# solar-shield.net
KiCad netlist of a schematic drawn in EAGLE
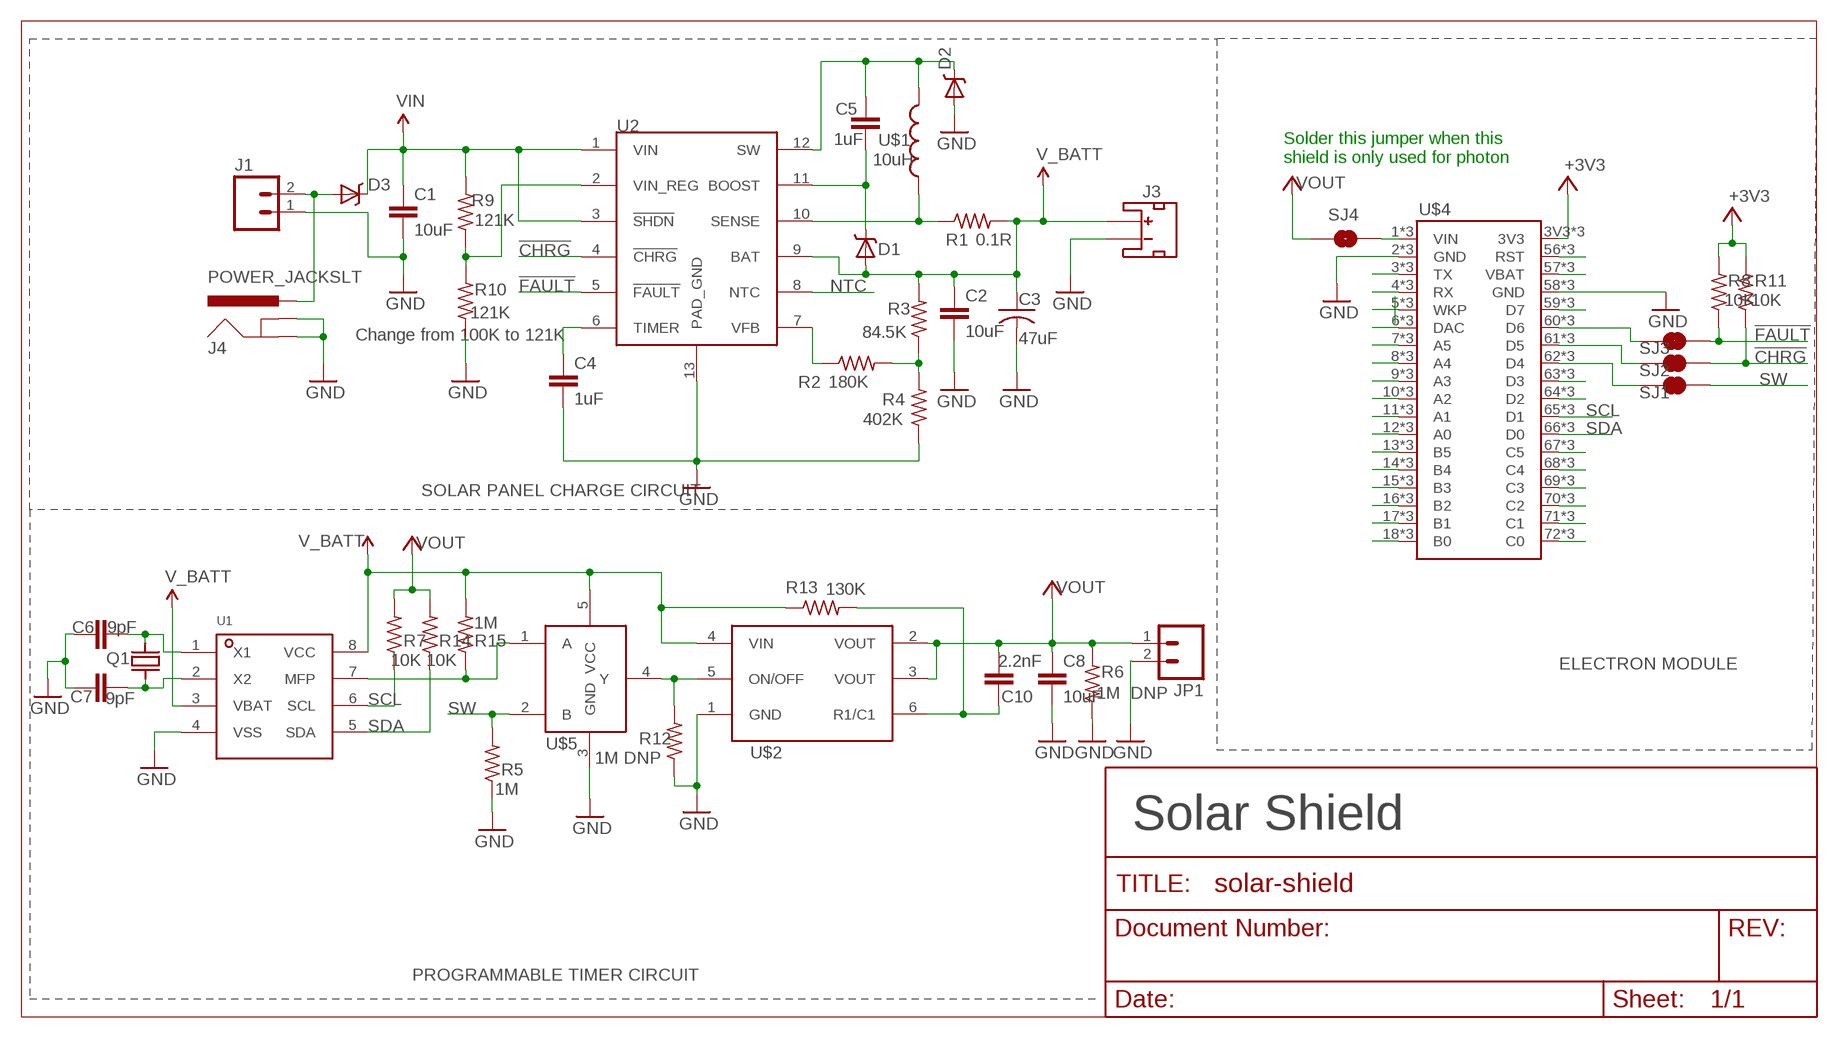
[diagram p0: schematic, sheet 1]

(export (version "E")
  (design (tool "Eeschema 10.0.6"))
  (components
    (comp (ref "C1")
      (value "10uF")
      (footprint "eagle-import:1206")
      (libsource (lib "eagle-import") (part "CAP_NONE_POLB"))
    )
    (comp (ref "C2")
      (value "10uF")
      (footprint "eagle-import:1206")
      (libsource (lib "eagle-import") (part "CAP_NONE_POLB"))
    )
    (comp (ref "C3")
      (value "47uF")
      (footprint "eagle-import:47U_TAN")
      (libsource (lib "eagle-import") (part "C-USB"))
    )
    (comp (ref "C4")
      (value "1uF")
      (footprint "eagle-import:0603")
      (libsource (lib "eagle-import") (part "CAP_NONE_POL"))
    )
    (comp (ref "C5")
      (value "1uF")
      (footprint "eagle-import:0603")
      (libsource (lib "eagle-import") (part "CAP_NONE_POL"))
    )
    (comp (ref "C6")
      (value "9pF")
      (footprint "eagle-import:0603")
      (libsource (lib "eagle-import") (part "CAP_NONE_POL"))
    )
    (comp (ref "C7")
      (value "9pF")
      (footprint "eagle-import:0603")
      (libsource (lib "eagle-import") (part "CAP_NONE_POL"))
    )
    (comp (ref "C8")
      (value "10uF")
      (footprint "eagle-import:0805")
      (libsource (lib "eagle-import") (part "CAP_NONE_POLA"))
    )
    (comp (ref "C10")
      (value "2.2nF")
      (footprint "eagle-import:0603")
      (libsource (lib "eagle-import") (part "CAP_NONE_POL"))
    )
    (comp (ref "D1")
      (value "DIODE_SCHOTTKYD")
      (footprint "eagle-import:DIODE_SOD323")
      (libsource (lib "eagle-import") (part "DIODE_SCHOTTKYD"))
    )
    (comp (ref "D2")
      (value "DIODE_SCHOTTKYA")
      (footprint "eagle-import:DIODE_SMA")
      (libsource (lib "eagle-import") (part "DIODE_SCHOTTKYA"))
    )
    (comp (ref "D3")
      (value "DIODE_SCHOTTKYA")
      (footprint "eagle-import:DIODE_SMA")
      (libsource (lib "eagle-import") (part "DIODE_SCHOTTKYA"))
    )
    (comp (ref "J1")
      (value "M025MM")
      (footprint "eagle-import:SCREWTERMINAL-5MM-2")
      (libsource (lib "eagle-import") (part "M025MM"))
    )
    (comp (ref "J3")
      (value "JST_2MM_MALEA")
      (footprint "eagle-import:JST_2_MSD_VERT")
      (libsource (lib "eagle-import") (part "JST_2MM_MALEA"))
    )
    (comp (ref "J4")
      (value "POWER_JACKSLT")
      (footprint "eagle-import:POWER_JACK_SLOT")
      (libsource (lib "eagle-import") (part "POWER_JACKSLT"))
    )
    (comp (ref "JP1")
      (value "M02PTH")
      (footprint "eagle-import:1X02")
      (libsource (lib "eagle-import") (part "M02PTH"))
    )
    (comp (ref "Q1")
      (value "Q_FC135")
      (footprint "eagle-import:FC135")
      (libsource (lib "eagle-import") (part "Q_FC135"))
    )
    (comp (ref "R1")
      (value "0.1R")
      (footprint "eagle-import:R0805")
      (libsource (lib "eagle-import") (part "R-US_B"))
    )
    (comp (ref "R2")
      (value "180K")
      (footprint "eagle-import:0603")
      (libsource (lib "eagle-import") (part "R_0603"))
    )
    (comp (ref "R3")
      (value "84.5K")
      (footprint "eagle-import:0603")
      (libsource (lib "eagle-import") (part "R_0603"))
    )
    (comp (ref "R4")
      (value "402K")
      (footprint "eagle-import:0603")
      (libsource (lib "eagle-import") (part "R_0603"))
    )
    (comp (ref "R5")
      (value "1M")
      (footprint "eagle-import:0603")
      (libsource (lib "eagle-import") (part "R_0603"))
    )
    (comp (ref "R6")
      (value "1M DNP")
      (footprint "eagle-import:0603")
      (libsource (lib "eagle-import") (part "R_0603"))
    )
    (comp (ref "R7")
      (value "10K")
      (footprint "eagle-import:0603")
      (libsource (lib "eagle-import") (part "R_0603"))
    )
    (comp (ref "R8")
      (value "10K")
      (footprint "eagle-import:0603")
      (libsource (lib "eagle-import") (part "R_0603"))
    )
    (comp (ref "R9")
      (value "121K")
      (footprint "eagle-import:0603")
      (libsource (lib "eagle-import") (part "R_0603"))
    )
    (comp (ref "R10")
      (value "121K")
      (footprint "eagle-import:0603")
      (libsource (lib "eagle-import") (part "R_0603"))
    )
    (comp (ref "R11")
      (value "10K")
      (footprint "eagle-import:0603")
      (libsource (lib "eagle-import") (part "R_0603"))
    )
    (comp (ref "R12")
      (value "1M DNP")
      (footprint "eagle-import:0603")
      (libsource (lib "eagle-import") (part "R_0603"))
    )
    (comp (ref "R13")
      (value "130K")
      (footprint "eagle-import:0603")
      (libsource (lib "eagle-import") (part "R_0603"))
    )
    (comp (ref "R14")
      (value "10K")
      (footprint "eagle-import:0603")
      (libsource (lib "eagle-import") (part "R_0603"))
    )
    (comp (ref "R15")
      (value "1M")
      (footprint "eagle-import:0603")
      (libsource (lib "eagle-import") (part "R_0603"))
    )
    (comp (ref "SJ1")
      (value "JUMPER-PAD-2-NC_BY_TRACE")
      (footprint "eagle-import:PAD-JUMPER-2-NC_BY_TRACE_YES_SILK")
      (libsource (lib "eagle-import") (part "JUMPER-PAD-2-NC_BY_TRACE"))
    )
    (comp (ref "SJ2")
      (value "JUMPER-PAD-2-NC_BY_TRACE")
      (footprint "eagle-import:PAD-JUMPER-2-NC_BY_TRACE_YES_SILK")
      (libsource (lib "eagle-import") (part "JUMPER-PAD-2-NC_BY_TRACE"))
    )
    (comp (ref "SJ3")
      (value "JUMPER-PAD-2-NC_BY_TRACE")
      (footprint "eagle-import:PAD-JUMPER-2-NC_BY_TRACE_YES_SILK")
      (libsource (lib "eagle-import") (part "JUMPER-PAD-2-NC_BY_TRACE"))
    )
    (comp (ref "SJ4")
      (value "JUMPER-PAD-2-NO")
      (footprint "eagle-import:PAD-JUMPER-2-NO_NO_SILK")
      (libsource (lib "eagle-import") (part "JUMPER-PAD-2-NO"))
    )
    (comp (ref "U$1")
      (value "10uH")
      (footprint "eagle-import:INDUCTOR_NR6045T100M")
      (libsource (lib "eagle-import") (part "INDUCTORR"))
    )
    (comp (ref "U$2")
      (value "TPS27082L")
      (footprint "eagle-import:TPS27082L")
      (libsource (lib "eagle-import") (part "TPS27082L"))
    )
    (comp (ref "U$4")
      (value "ELECTRONDUALROW")
      (footprint "eagle-import:ELECTRON_DUAL-ROW")
      (libsource (lib "eagle-import") (part "ELECTRONDUALROW"))
    )
    (comp (ref "U$5")
      (value "SN74UP1G32A")
      (footprint "eagle-import:SN74UP1G32_DBV")
      (libsource (lib "eagle-import") (part "SN74UP1G32A"))
    )
    (comp (ref "U1")
      (value "RTC_MCP7941X")
      (footprint "eagle-import:RTC_MCP7941X")
      (libsource (lib "eagle-import") (part "RTC_MCP7941X"))
    )
    (comp (ref "U2")
      (value "LT3652A")
      (footprint "eagle-import:DFN_3X3")
      (libsource (lib "eagle-import") (part "LT3652A"))
    )
  )
  (nets
    (net (code "1") (name "+3V3") (class "Default")
      (node (ref "R11") (pin "2") (pinfunction "2_2") (pintype "passive"))
      (node (ref "R8") (pin "2") (pinfunction "2_2") (pintype "passive"))
      (node (ref "U$4") (pin "3V3") (pinfunction "3V3_3V3") (pintype "power_in"))
      (node (ref "U$4") (pin "55") (pinfunction "3V3_55") (pintype "power_in"))
      (node (ref "U$4") (pin "91") (pinfunction "3V3_91") (pintype "power_in"))
    )
    (net (code "2") (name "/N$10") (class "Default")
      (node (ref "U$4") (pin "3") (pinfunction "TX_3") (pintype "bidirectional"))
      (node (ref "U$4") (pin "39") (pinfunction "TX_39") (pintype "bidirectional"))
      (node (ref "U$4") (pin "TX") (pinfunction "TX_TX") (pintype "bidirectional"))
    )
    (net (code "3") (name "/NTC") (class "Default")
      (node (ref "U2") (pin "8") (pinfunction "NTC_8") (pintype "bidirectional"))
    )
    (net (code "4") (name "/SCL") (class "Default")
      (node (ref "R7") (pin "1") (pinfunction "1_1") (pintype "passive"))
      (node (ref "U$4") (pin "101") (pinfunction "D1_101") (pintype "bidirectional"))
      (node (ref "U$4") (pin "65") (pinfunction "D1_65") (pintype "bidirectional"))
      (node (ref "U$4") (pin "D1") (pinfunction "D1_D1") (pintype "bidirectional"))
      (node (ref "U1") (pin "6") (pinfunction "SCL_6") (pintype "bidirectional"))
    )
    (net (code "5") (name "/SDA") (class "Default")
      (node (ref "R14") (pin "1") (pinfunction "1_1") (pintype "passive"))
      (node (ref "U$4") (pin "102") (pinfunction "D0_102") (pintype "bidirectional"))
      (node (ref "U$4") (pin "66") (pinfunction "D0_66") (pintype "bidirectional"))
      (node (ref "U$4") (pin "D0") (pinfunction "D0_D0") (pintype "bidirectional"))
      (node (ref "U1") (pin "5") (pinfunction "SDA_5") (pintype "bidirectional"))
    )
    (net (code "6") (name "/SW") (class "Default")
      (node (ref "R5") (pin "2") (pinfunction "2_2") (pintype "passive"))
      (node (ref "SJ1") (pin "2") (pinfunction "2_2") (pintype "passive"))
      (node (ref "U$5") (pin "2") (pinfunction "B_2") (pintype "bidirectional"))
    )
    (net (code "7") (name "/~{CHRG}") (class "Default")
      (node (ref "R11") (pin "1") (pinfunction "1_1") (pintype "passive"))
      (node (ref "SJ2") (pin "2") (pinfunction "2_2") (pintype "passive"))
      (node (ref "U2") (pin "4") (pinfunction "~{CHRG}_4") (pintype "bidirectional"))
    )
    (net (code "8") (name "/~{FAULT}") (class "Default")
      (node (ref "R8") (pin "1") (pinfunction "1_1") (pintype "passive"))
      (node (ref "SJ3") (pin "2") (pinfunction "2_2") (pintype "passive"))
      (node (ref "U2") (pin "5") (pinfunction "~{FAULT}_5") (pintype "bidirectional"))
    )
    (net (code "9") (name "GND") (class "Default")
      (node (ref "C1") (pin "2") (pinfunction "CATHODE_2") (pintype "passive"))
      (node (ref "C2") (pin "2") (pinfunction "CATHODE_2") (pintype "passive"))
      (node (ref "C3") (pin "C") (pinfunction "2_C") (pintype "passive"))
      (node (ref "C4") (pin "2") (pinfunction "CATHODE_2") (pintype "passive"))
      (node (ref "C6") (pin "1") (pinfunction "ANODE_1") (pintype "passive"))
      (node (ref "C7") (pin "1") (pinfunction "ANODE_1") (pintype "passive"))
      (node (ref "C8") (pin "2") (pinfunction "CATHODE_2") (pintype "passive"))
      (node (ref "D2") (pin "ANODE") (pinfunction "ANODE_ANODE") (pintype "passive"))
      (node (ref "J1") (pin "1") (pinfunction "1_1") (pintype "passive"))
      (node (ref "J3") (pin "GND") (pinfunction "-_GND") (pintype "bidirectional"))
      (node (ref "J4") (pin "GND@1") (pinfunction "GNDBREAK_GND@1") (pintype "bidirectional"))
      (node (ref "J4") (pin "GND@2") (pinfunction "GND_GND@2") (pintype "bidirectional"))
      (node (ref "JP1") (pin "2") (pinfunction "2_2") (pintype "passive"))
      (node (ref "R10") (pin "1") (pinfunction "1_1") (pintype "passive"))
      (node (ref "R12") (pin "1") (pinfunction "1_1") (pintype "passive"))
      (node (ref "R4") (pin "1") (pinfunction "1_1") (pintype "passive"))
      (node (ref "R5") (pin "1") (pinfunction "1_1") (pintype "passive"))
      (node (ref "R6") (pin "1") (pinfunction "1_1") (pintype "passive"))
      (node (ref "U$2") (pin "1") (pinfunction "GND_1") (pintype "bidirectional"))
      (node (ref "U$4") (pin "2") (pinfunction "GND_2") (pintype "power_in"))
      (node (ref "U$4") (pin "38") (pinfunction "GND_38") (pintype "power_in"))
      (node (ref "U$4") (pin "58") (pinfunction "GND_58") (pintype "power_in"))
      (node (ref "U$4") (pin "94") (pinfunction "GND_94") (pintype "power_in"))
      (node (ref "U$4") (pin "GND") (pinfunction "GND_GND") (pintype "power_in"))
      (node (ref "U$4") (pin "GND@2") (pinfunction "GND_GND@2") (pintype "power_in"))
      (node (ref "U$5") (pin "3") (pinfunction "GND_3") (pintype "bidirectional"))
      (node (ref "U1") (pin "4") (pinfunction "VSS_4") (pintype "bidirectional"))
      (node (ref "U2") (pin "13") (pinfunction "PAD_GND_13") (pintype "bidirectional"))
    )
    (net (code "10") (name "Net-(C4-ANODE)") (class "Default")
      (node (ref "C4") (pin "1") (pinfunction "ANODE_1") (pintype "passive"))
      (node (ref "U2") (pin "6") (pinfunction "TIMER_6") (pintype "bidirectional"))
    )
    (net (code "11") (name "Net-(C5-ANODE)") (class "Default")
      (node (ref "C5") (pin "1") (pinfunction "ANODE_1") (pintype "passive"))
      (node (ref "D2") (pin "CATHODE") (pinfunction "CATHODE_CATHODE") (pintype "passive"))
      (node (ref "U$1") (pin "P$2") (pinfunction "2_P$2") (pintype "passive"))
      (node (ref "U2") (pin "12") (pinfunction "SW_12") (pintype "bidirectional"))
    )
    (net (code "12") (name "Net-(C5-CATHODE)") (class "Default")
      (node (ref "C5") (pin "2") (pinfunction "CATHODE_2") (pintype "passive"))
      (node (ref "D1") (pin "CATHODE") (pinfunction "CATHODE_CATHODE") (pintype "passive"))
      (node (ref "U2") (pin "11") (pinfunction "BOOST_11") (pintype "bidirectional"))
    )
    (net (code "13") (name "Net-(C6-CATHODE)") (class "Default")
      (node (ref "C6") (pin "2") (pinfunction "CATHODE_2") (pintype "passive"))
      (node (ref "Q1") (pin "X2") (pinfunction "2_X2") (pintype "passive"))
      (node (ref "U1") (pin "1") (pinfunction "X1_1") (pintype "bidirectional"))
    )
    (net (code "14") (name "Net-(C7-CATHODE)") (class "Default")
      (node (ref "C7") (pin "2") (pinfunction "CATHODE_2") (pintype "passive"))
      (node (ref "Q1") (pin "X1") (pinfunction "1_X1") (pintype "passive"))
      (node (ref "U1") (pin "2") (pinfunction "X2_2") (pintype "bidirectional"))
    )
    (net (code "15") (name "Net-(C10-ANODE)") (class "Default")
      (node (ref "C10") (pin "1") (pinfunction "ANODE_1") (pintype "passive"))
      (node (ref "R13") (pin "2") (pinfunction "2_2") (pintype "passive"))
      (node (ref "U$2") (pin "6") (pinfunction "R1/C1_6") (pintype "bidirectional"))
    )
    (net (code "16") (name "Net-(D3-PadANODE)") (class "Default")
      (node (ref "D3") (pin "ANODE") (pinfunction "ANODE_ANODE") (pintype "passive"))
      (node (ref "J1") (pin "2") (pinfunction "2_2") (pintype "passive"))
      (node (ref "J4") (pin "PWR") (pinfunction "PWR_PWR") (pintype "bidirectional"))
    )
    (net (code "17") (name "Net-(R2-Pad2)") (class "Default")
      (node (ref "R2") (pin "2") (pinfunction "2_2") (pintype "passive"))
      (node (ref "R3") (pin "1") (pinfunction "1_1") (pintype "passive"))
      (node (ref "R4") (pin "2") (pinfunction "2_2") (pintype "passive"))
    )
    (net (code "18") (name "Net-(SJ1-Pad1)") (class "Default")
      (node (ref "SJ1") (pin "1") (pinfunction "1_1") (pintype "passive"))
      (node (ref "U$4") (pin "62") (pinfunction "D4_62") (pintype "bidirectional"))
      (node (ref "U$4") (pin "98") (pinfunction "D4_98") (pintype "bidirectional"))
      (node (ref "U$4") (pin "D4") (pinfunction "D4_D4") (pintype "bidirectional"))
    )
    (net (code "19") (name "Net-(SJ2-Pad1)") (class "Default")
      (node (ref "SJ2") (pin "1") (pinfunction "1_1") (pintype "passive"))
      (node (ref "U$4") (pin "61") (pinfunction "D5_61") (pintype "bidirectional"))
      (node (ref "U$4") (pin "97") (pinfunction "D5_97") (pintype "bidirectional"))
      (node (ref "U$4") (pin "D5") (pinfunction "D5_D5") (pintype "bidirectional"))
    )
    (net (code "20") (name "Net-(SJ3-Pad1)") (class "Default")
      (node (ref "SJ3") (pin "1") (pinfunction "1_1") (pintype "passive"))
      (node (ref "U$4") (pin "60") (pinfunction "D6_60") (pintype "bidirectional"))
      (node (ref "U$4") (pin "96") (pinfunction "D6_96") (pintype "bidirectional"))
      (node (ref "U$4") (pin "D6") (pinfunction "D6_D6") (pintype "bidirectional"))
    )
    (net (code "21") (name "Net-(SJ4-Pad2)") (class "Default")
      (node (ref "SJ4") (pin "2") (pinfunction "2_2") (pintype "passive"))
      (node (ref "U$4") (pin "1") (pinfunction "VIN_1") (pintype "power_in"))
      (node (ref "U$4") (pin "37") (pinfunction "VIN_37") (pintype "power_in"))
      (node (ref "U$4") (pin "VIN") (pinfunction "VIN_VIN") (pintype "power_in"))
    )
    (net (code "22") (name "Net-(U$1-1)") (class "Default")
      (node (ref "R1") (pin "1") (pinfunction "1_1") (pintype "passive"))
      (node (ref "U$1") (pin "P$1") (pinfunction "1_P$1") (pintype "passive"))
      (node (ref "U2") (pin "10") (pinfunction "SENSE_10") (pintype "bidirectional"))
    )
    (net (code "23") (name "Net-(U$2-ON{slash}OFF)") (class "Default")
      (node (ref "R12") (pin "2") (pinfunction "2_2") (pintype "passive"))
      (node (ref "U$2") (pin "5") (pinfunction "ON/OFF_5") (pintype "bidirectional"))
      (node (ref "U$5") (pin "4") (pinfunction "Y_4") (pintype "bidirectional"))
    )
    (net (code "24") (name "Net-(U$4-A0-Pad12)") (class "Default")
      (node (ref "U$4") (pin "12") (pinfunction "A0_12") (pintype "bidirectional"))
      (node (ref "U$4") (pin "48") (pinfunction "A0_48") (pintype "bidirectional"))
      (node (ref "U$4") (pin "A0") (pinfunction "A0_A0") (pintype "bidirectional"))
    )
    (net (code "25") (name "Net-(U$4-A1-Pad11)") (class "Default")
      (node (ref "U$4") (pin "11") (pinfunction "A1_11") (pintype "bidirectional"))
      (node (ref "U$4") (pin "47") (pinfunction "A1_47") (pintype "bidirectional"))
      (node (ref "U$4") (pin "A1") (pinfunction "A1_A1") (pintype "bidirectional"))
    )
    (net (code "26") (name "Net-(U$4-A2-Pad10)") (class "Default")
      (node (ref "U$4") (pin "10") (pinfunction "A2_10") (pintype "bidirectional"))
      (node (ref "U$4") (pin "46") (pinfunction "A2_46") (pintype "bidirectional"))
      (node (ref "U$4") (pin "A2") (pinfunction "A2_A2") (pintype "bidirectional"))
    )
    (net (code "27") (name "Net-(U$4-A3-Pad45)") (class "Default")
      (node (ref "U$4") (pin "45") (pinfunction "A3_45") (pintype "bidirectional"))
      (node (ref "U$4") (pin "9") (pinfunction "A3_9") (pintype "bidirectional"))
      (node (ref "U$4") (pin "A3") (pinfunction "A3_A3") (pintype "bidirectional"))
    )
    (net (code "28") (name "Net-(U$4-A4-Pad44)") (class "Default")
      (node (ref "U$4") (pin "44") (pinfunction "A4_44") (pintype "bidirectional"))
      (node (ref "U$4") (pin "8") (pinfunction "A4_8") (pintype "bidirectional"))
      (node (ref "U$4") (pin "A4") (pinfunction "A4_A4") (pintype "bidirectional"))
    )
    (net (code "29") (name "Net-(U$4-A5-Pad43)") (class "Default")
      (node (ref "U$4") (pin "43") (pinfunction "A5_43") (pintype "bidirectional"))
      (node (ref "U$4") (pin "7") (pinfunction "A5_7") (pintype "bidirectional"))
      (node (ref "U$4") (pin "A5") (pinfunction "A5_A5") (pintype "bidirectional"))
    )
    (net (code "30") (name "Net-(U$4-B0-Pad18)") (class "Default")
      (node (ref "U$4") (pin "18") (pinfunction "B0_18") (pintype "bidirectional"))
      (node (ref "U$4") (pin "54") (pinfunction "B0_54") (pintype "bidirectional"))
      (node (ref "U$4") (pin "B0") (pinfunction "B0_B0") (pintype "bidirectional"))
    )
    (net (code "31") (name "Net-(U$4-B1-Pad17)") (class "Default")
      (node (ref "U$4") (pin "17") (pinfunction "B1_17") (pintype "bidirectional"))
      (node (ref "U$4") (pin "53") (pinfunction "B1_53") (pintype "bidirectional"))
      (node (ref "U$4") (pin "B1") (pinfunction "B1_B1") (pintype "bidirectional"))
    )
    (net (code "32") (name "Net-(U$4-B2-Pad16)") (class "Default")
      (node (ref "U$4") (pin "16") (pinfunction "B2_16") (pintype "bidirectional"))
      (node (ref "U$4") (pin "52") (pinfunction "B2_52") (pintype "bidirectional"))
      (node (ref "U$4") (pin "B2") (pinfunction "B2_B2") (pintype "bidirectional"))
    )
    (net (code "33") (name "Net-(U$4-B3-Pad15)") (class "Default")
      (node (ref "U$4") (pin "15") (pinfunction "B3_15") (pintype "bidirectional"))
      (node (ref "U$4") (pin "51") (pinfunction "B3_51") (pintype "bidirectional"))
      (node (ref "U$4") (pin "B3") (pinfunction "B3_B3") (pintype "bidirectional"))
    )
    (net (code "34") (name "Net-(U$4-B4-Pad14)") (class "Default")
      (node (ref "U$4") (pin "14") (pinfunction "B4_14") (pintype "bidirectional"))
      (node (ref "U$4") (pin "50") (pinfunction "B4_50") (pintype "bidirectional"))
      (node (ref "U$4") (pin "B4") (pinfunction "B4_B4") (pintype "bidirectional"))
    )
    (net (code "35") (name "Net-(U$4-B5-Pad13)") (class "Default")
      (node (ref "U$4") (pin "13") (pinfunction "B5_13") (pintype "bidirectional"))
      (node (ref "U$4") (pin "49") (pinfunction "B5_49") (pintype "bidirectional"))
      (node (ref "U$4") (pin "B5") (pinfunction "B5_B5") (pintype "bidirectional"))
    )
    (net (code "36") (name "Net-(U$4-C0-Pad108)") (class "Default")
      (node (ref "U$4") (pin "108") (pinfunction "C0_108") (pintype "bidirectional"))
      (node (ref "U$4") (pin "72") (pinfunction "C0_72") (pintype "bidirectional"))
      (node (ref "U$4") (pin "C0") (pinfunction "C0_C0") (pintype "bidirectional"))
    )
    (net (code "37") (name "Net-(U$4-C1-Pad107)") (class "Default")
      (node (ref "U$4") (pin "107") (pinfunction "C1_107") (pintype "bidirectional"))
      (node (ref "U$4") (pin "71") (pinfunction "C1_71") (pintype "bidirectional"))
      (node (ref "U$4") (pin "C1") (pinfunction "C1_C1") (pintype "bidirectional"))
    )
    (net (code "38") (name "Net-(U$4-C2-Pad106)") (class "Default")
      (node (ref "U$4") (pin "106") (pinfunction "C2_106") (pintype "bidirectional"))
      (node (ref "U$4") (pin "70") (pinfunction "C2_70") (pintype "bidirectional"))
      (node (ref "U$4") (pin "C2") (pinfunction "C2_C2") (pintype "bidirectional"))
    )
    (net (code "39") (name "Net-(U$4-C3-Pad105)") (class "Default")
      (node (ref "U$4") (pin "105") (pinfunction "C3_105") (pintype "bidirectional"))
      (node (ref "U$4") (pin "69") (pinfunction "C3_69") (pintype "bidirectional"))
      (node (ref "U$4") (pin "C3") (pinfunction "C3_C3") (pintype "bidirectional"))
    )
    (net (code "40") (name "Net-(U$4-C4-Pad104)") (class "Default")
      (node (ref "U$4") (pin "104") (pinfunction "C4_104") (pintype "bidirectional"))
      (node (ref "U$4") (pin "68") (pinfunction "C4_68") (pintype "bidirectional"))
      (node (ref "U$4") (pin "C4") (pinfunction "C4_C4") (pintype "bidirectional"))
    )
    (net (code "41") (name "Net-(U$4-C5-Pad103)") (class "Default")
      (node (ref "U$4") (pin "103") (pinfunction "C5_103") (pintype "bidirectional"))
      (node (ref "U$4") (pin "67") (pinfunction "C5_67") (pintype "bidirectional"))
      (node (ref "U$4") (pin "C5") (pinfunction "C5_C5") (pintype "bidirectional"))
    )
    (net (code "42") (name "Net-(U$4-D2-Pad100)") (class "Default")
      (node (ref "U$4") (pin "100") (pinfunction "D2_100") (pintype "bidirectional"))
      (node (ref "U$4") (pin "64") (pinfunction "D2_64") (pintype "bidirectional"))
      (node (ref "U$4") (pin "D2") (pinfunction "D2_D2") (pintype "bidirectional"))
    )
    (net (code "43") (name "Net-(U$4-D3-Pad63)") (class "Default")
      (node (ref "U$4") (pin "63") (pinfunction "D3_63") (pintype "bidirectional"))
      (node (ref "U$4") (pin "99") (pinfunction "D3_99") (pintype "bidirectional"))
      (node (ref "U$4") (pin "D3") (pinfunction "D3_D3") (pintype "bidirectional"))
    )
    (net (code "44") (name "Net-(U$4-D7-Pad59)") (class "Default")
      (node (ref "U$4") (pin "59") (pinfunction "D7_59") (pintype "bidirectional"))
      (node (ref "U$4") (pin "95") (pinfunction "D7_95") (pintype "bidirectional"))
      (node (ref "U$4") (pin "D7") (pinfunction "D7_D7") (pintype "bidirectional"))
    )
    (net (code "45") (name "Net-(U$4-DAC-Pad42)") (class "Default")
      (node (ref "U$4") (pin "42") (pinfunction "DAC_42") (pintype "bidirectional"))
      (node (ref "U$4") (pin "6") (pinfunction "DAC_6") (pintype "bidirectional"))
      (node (ref "U$4") (pin "DAC") (pinfunction "DAC_DAC") (pintype "bidirectional"))
    )
    (net (code "46") (name "Net-(U$4-PadRST)") (class "Default")
      (node (ref "U$4") (pin "56") (pinfunction "RST_56") (pintype "bidirectional"))
      (node (ref "U$4") (pin "92") (pinfunction "RST_92") (pintype "bidirectional"))
      (node (ref "U$4") (pin "RST") (pinfunction "RST_RST") (pintype "bidirectional"))
    )
    (net (code "47") (name "Net-(U$4-PadRX)") (class "Default")
      (node (ref "U$4") (pin "4") (pinfunction "RX_4") (pintype "bidirectional"))
      (node (ref "U$4") (pin "40") (pinfunction "RX_40") (pintype "bidirectional"))
      (node (ref "U$4") (pin "RX") (pinfunction "RX_RX") (pintype "bidirectional"))
    )
    (net (code "48") (name "Net-(U$4-PadVBAT)") (class "Default")
      (node (ref "U$4") (pin "57") (pinfunction "VBAT_57") (pintype "passive"))
      (node (ref "U$4") (pin "93") (pinfunction "VBAT_93") (pintype "passive"))
      (node (ref "U$4") (pin "VBAT") (pinfunction "VBAT_VBAT") (pintype "passive"))
    )
    (net (code "49") (name "Net-(U$4-PadWKP)") (class "Default")
      (node (ref "U$4") (pin "41") (pinfunction "WKP_41") (pintype "bidirectional"))
      (node (ref "U$4") (pin "5") (pinfunction "WKP_5") (pintype "bidirectional"))
      (node (ref "U$4") (pin "WKP") (pinfunction "WKP_WKP") (pintype "bidirectional"))
    )
    (net (code "50") (name "Net-(U$5-A)") (class "Default")
      (node (ref "R15") (pin "1") (pinfunction "1_1") (pintype "passive"))
      (node (ref "U$5") (pin "1") (pinfunction "A_1") (pintype "bidirectional"))
      (node (ref "U1") (pin "7") (pinfunction "MFP_7") (pintype "bidirectional"))
    )
    (net (code "51") (name "Net-(U2-VFB)") (class "Default")
      (node (ref "R2") (pin "1") (pinfunction "1_1") (pintype "passive"))
      (node (ref "U2") (pin "7") (pinfunction "VFB_7") (pintype "bidirectional"))
    )
    (net (code "52") (name "Net-(U2-VIN_REG)") (class "Default")
      (node (ref "R10") (pin "2") (pinfunction "2_2") (pintype "passive"))
      (node (ref "R9") (pin "1") (pinfunction "1_1") (pintype "passive"))
      (node (ref "U2") (pin "2") (pinfunction "VIN_REG_2") (pintype "bidirectional"))
    )
    (net (code "53") (name "VIN") (class "Default")
      (node (ref "C1") (pin "1") (pinfunction "ANODE_1") (pintype "passive"))
      (node (ref "D3") (pin "CATHODE") (pinfunction "CATHODE_CATHODE") (pintype "passive"))
      (node (ref "R9") (pin "2") (pinfunction "2_2") (pintype "passive"))
      (node (ref "U2") (pin "1") (pinfunction "VIN_1") (pintype "bidirectional"))
      (node (ref "U2") (pin "3") (pinfunction "~{SHDN}_3") (pintype "bidirectional"))
    )
    (net (code "54") (name "VOUT") (class "Default")
      (node (ref "C10") (pin "2") (pinfunction "CATHODE_2") (pintype "passive"))
      (node (ref "C8") (pin "1") (pinfunction "ANODE_1") (pintype "passive"))
      (node (ref "JP1") (pin "1") (pinfunction "1_1") (pintype "passive"))
      (node (ref "R14") (pin "2") (pinfunction "2_2") (pintype "passive"))
      (node (ref "R6") (pin "2") (pinfunction "2_2") (pintype "passive"))
      (node (ref "R7") (pin "2") (pinfunction "2_2") (pintype "passive"))
      (node (ref "SJ4") (pin "1") (pinfunction "1_1") (pintype "passive"))
      (node (ref "U$2") (pin "2") (pinfunction "VOUT_2") (pintype "bidirectional"))
      (node (ref "U$2") (pin "3") (pinfunction "VOUT_3") (pintype "bidirectional"))
    )
    (net (code "55") (name "V_BATT") (class "Default")
      (node (ref "C2") (pin "1") (pinfunction "ANODE_1") (pintype "passive"))
      (node (ref "C3") (pin "A") (pinfunction "1_A") (pintype "passive"))
      (node (ref "D1") (pin "ANODE") (pinfunction "ANODE_ANODE") (pintype "passive"))
      (node (ref "J3") (pin "VCC") (pinfunction "+_VCC") (pintype "bidirectional"))
      (node (ref "R1") (pin "2") (pinfunction "2_2") (pintype "passive"))
      (node (ref "R13") (pin "1") (pinfunction "1_1") (pintype "passive"))
      (node (ref "R15") (pin "2") (pinfunction "2_2") (pintype "passive"))
      (node (ref "R3") (pin "2") (pinfunction "2_2") (pintype "passive"))
      (node (ref "U$2") (pin "4") (pinfunction "VIN_4") (pintype "bidirectional"))
      (node (ref "U$5") (pin "5") (pinfunction "VCC_5") (pintype "bidirectional"))
      (node (ref "U1") (pin "3") (pinfunction "VBAT_3") (pintype "bidirectional"))
      (node (ref "U1") (pin "8") (pinfunction "VCC_8") (pintype "bidirectional"))
      (node (ref "U2") (pin "9") (pinfunction "BAT_9") (pintype "bidirectional"))
    )
    (net (code "56") (name "unconnected-(J3-PAD1-PadP$1)") (class "Default")
      (node (ref "J3") (pin "P$1") (pinfunction "PAD1_P$1") (pintype "bidirectional"))
    )
    (net (code "57") (name "unconnected-(J3-PAD2-PadP$2)") (class "Default")
      (node (ref "J3") (pin "P$2") (pinfunction "PAD2_P$2") (pintype "bidirectional"))
    )
  )
)
